# CANBUS.net
KiCad netlist of a schematic drawn in Altium Designer
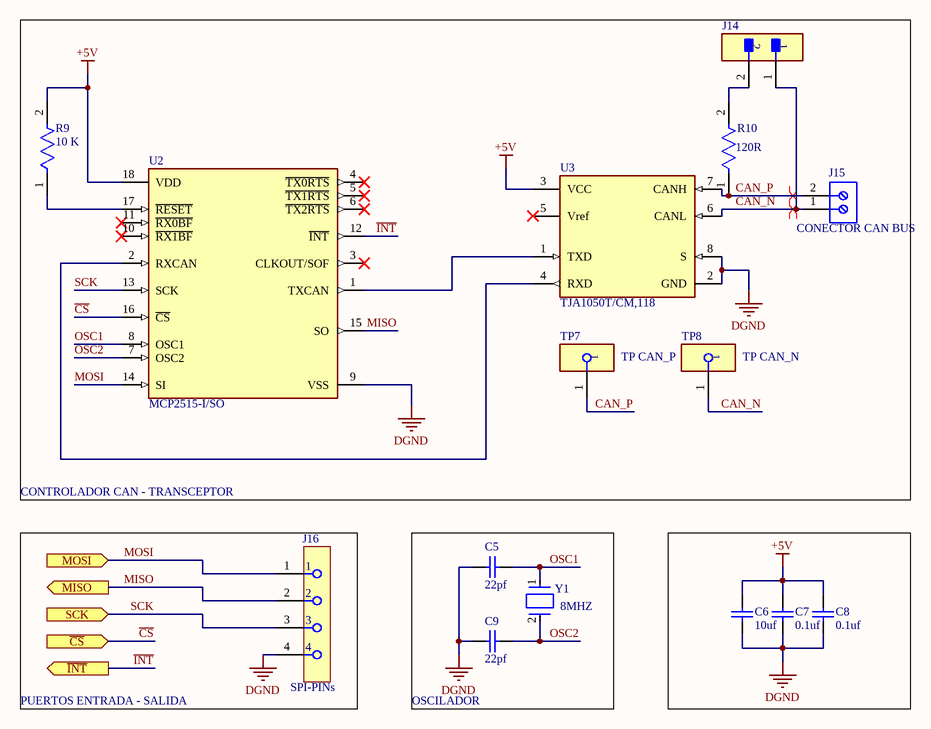
[diagram p0: CANBUS.SchDoc]

(export (version "E")
  (design (tool "Eeschema 10.0.6"))
  (components
    (comp (ref "C5")
      (value "22pf")
      (footprint "CAPC2013X145X50NL20T25")
      (description "CAP 22pf 20% 0805")
      (fields (field (name "MANUFACTURER") "Kemet") (field (name "PART NUMBER") "C0805S104K5RACTU"))
      (libsource (lib "Altium Content Vault") (part "CAP"))
    )
    (comp (ref "C6")
      (value "10uf")
      (footprint "CAPC2013X145X50NL20T25")
      (description "CAP 10uf 20% 0805")
      (fields (field (name "MANUFACTURER") "Kemet") (field (name "PART NUMBER") "C0805S104K5RACTU"))
      (libsource (lib "Altium Content Vault") (part "CAP"))
    )
    (comp (ref "C7")
      (value "0.1uf")
      (footprint "CAPC2013X145X50NL20T25")
      (description "CAP 100nf 20% 0805")
      (fields (field (name "MANUFACTURER") "Kemet") (field (name "PART NUMBER") "C0805S104K5RACTU"))
      (libsource (lib "Altium Content Vault") (part "CAP"))
    )
    (comp (ref "C8")
      (value "0.1uf")
      (footprint "CAPC2013X145X50NL20T25")
      (description "CAP 100nf 20% 0805")
      (fields (field (name "MANUFACTURER") "Kemet") (field (name "PART NUMBER") "C0805S104K5RACTU"))
      (libsource (lib "Altium Content Vault") (part "CAP"))
    )
    (comp (ref "C9")
      (value "22pf")
      (footprint "CAPC2013X145X50NL20T25")
      (description "CAP 22pf 20% 0805")
      (fields (field (name "MANUFACTURER") "Kemet") (field (name "PART NUMBER") "C0805S104K5RACTU"))
      (libsource (lib "Altium Content Vault") (part "CAP"))
    )
    (comp (ref "J14")
      (value "TSW-102-07-F-S")
      (footprint "FP-TSW-102-07-F-S-MFG")
      (description "HEADER PINS 2 POS / Jumper de Res. Terminacion")
      (libsource (lib "Altium Content Vault") (part "3bc925449376181038e59eaffc5286c"))
    )
    (comp (ref "J15")
      (value "CONECTOR CAN BUS")
      (footprint "691102710002")
      (description "TERMINAL BLOCK 2 POS / Salida BUS CAN")
      (fields (field (name "VOLTAGE") "300V"))
      (libsource (lib "Altium Content Vault") (part "TBL - 1R - 02P - Screw"))
    )
    (comp (ref "J16")
      (value "SPI-PINs")
      (footprint "FP-ESW-104-23-G-S-MFG")
      (description "HEADER PINS 4 POS / SPI Pins")
      (libsource (lib "Altium Content Vault") (part "ESW-104-23-G-S"))
    )
    (comp (ref "R9")
      (value "10 K")
      (footprint "FP-AC0805-MFG")
      (description "RES 10K 5% 0805")
      (fields
        (field (name "MANUFACTURER PART NUMBER") "AC0805FR-072K2L")
        (field (name "MANUFACTURER") "Yageo")
      )
      (libsource (lib "Altium Content Vault") (part "1029c3af85768c4190bb7ad29bc67b5"))
    )
    (comp (ref "R10")
      (value "120R")
      (footprint "FP-RN73R2A-IPC_A")
      (description "RES 120R 5% 0805 / Resistencia de terminacion")
      (libsource (lib "Altium Content Vault") (part "1029c3af85768c4190bb7ad29bc67b5"))
    )
    (comp (ref "TP7")
      (value "TP CAN_P")
      (footprint "FP-5004-MFG")
      (description "PC TEST POINT MINIATURE YELLOW")
      (fields (field (name "MANUFACTURER") "Keystone") (field (name "MANUFACTURER PART NUMBER") "5004"))
      (libsource (lib "Altium Content Vault") (part "98815daf2f2c152b0c43f5ab9800df6"))
    )
    (comp (ref "TP8")
      (value "TP CAN_N")
      (footprint "FP-5004-MFG")
      (description "PC TEST POINT MINIATURE YELLOW")
      (fields (field (name "MANUFACTURER") "Keystone") (field (name "MANUFACTURER PART NUMBER") "5004"))
      (libsource (lib "Altium Content Vault") (part "98815daf2f2c152b0c43f5ab9800df6"))
    )
    (comp (ref "U2")
      (value "MCP2515-I/SO")
      (footprint "FP-C04-051-MFG")
      (description "CI MCP2515 SOIC18")
      (fields
        (field (name "MANUFACTURER") "Microchip")
        (field (name "OCTOPART") "https://octopart.com/mcp2515-i%2Fso-microchip-430187")
      )
      (libsource (lib "Altium Content Vault") (part "1c78ea6ff576bac94664e2637e1b479"))
    )
    (comp (ref "U3")
      (value "TJA1050T/CM,118")
      (footprint "FP-SOT96-1-IPC_A")
      (description "CI TJA1050 TRANSCEIVER SOIC8")
      (libsource (lib "Altium Content Vault") (part "cfdefafd38a55dc0607790f57b8a78f"))
    )
    (comp (ref "Y1")
      (value "8MHZ")
      (footprint "FP-ECS-80-20-4X-MFG")
      (description "CRYSTAL 8 MHz / CAN BUS")
      (fields (field (name "TOLERANCE") "0.003%"))
      (libsource (lib "Altium Content Vault") (part "c23a69dc6c9e2f18f2079038eb95dd1"))
    )
  )
  (nets
    (net (code "1") (name "+5V") (class "Default")
      (node (ref "C6") (pin "2") (pinfunction "2_2") (pintype "passive"))
      (node (ref "C7") (pin "2") (pinfunction "2_2") (pintype "passive"))
      (node (ref "C8") (pin "2") (pinfunction "2_2") (pintype "passive"))
      (node (ref "R9") (pin "2") (pinfunction "2_2") (pintype "passive"))
      (node (ref "U2") (pin "18") (pinfunction "VDD_18") (pintype "power_in"))
      (node (ref "U3") (pin "3") (pinfunction "VCC_3") (pintype "power_in"))
    )
    (net (code "2") (name "/CAN_N") (class "Default")
      (node (ref "J14") (pin "1") (pinfunction "1_1") (pintype "passive"))
      (node (ref "J15") (pin "1") (pinfunction "1_1") (pintype "passive"))
      (node (ref "TP8") (pin "1") (pinfunction "1_1") (pintype "passive"))
      (node (ref "U3") (pin "6") (pinfunction "CANL_6") (pintype "input"))
    )
    (net (code "3") (name "/CAN_P") (class "Default")
      (node (ref "J15") (pin "2") (pinfunction "2_2") (pintype "passive"))
      (node (ref "R10") (pin "1") (pinfunction "1_1") (pintype "passive"))
      (node (ref "TP7") (pin "1") (pinfunction "1_1") (pintype "passive"))
      (node (ref "U3") (pin "7") (pinfunction "CANH_7") (pintype "input"))
    )
    (net (code "4") (name "/MISO") (class "Default")
      (node (ref "J16") (pin "2") (pinfunction "2_2") (pintype "passive"))
      (node (ref "U2") (pin "15") (pinfunction "SO_15") (pintype "output"))
    )
    (net (code "5") (name "/MOSI") (class "Default")
      (node (ref "J16") (pin "1") (pinfunction "1_1") (pintype "passive"))
      (node (ref "U2") (pin "14") (pinfunction "SI_14") (pintype "input"))
    )
    (net (code "6") (name "/OSC1") (class "Default")
      (node (ref "C5") (pin "2") (pinfunction "2_2") (pintype "passive"))
      (node (ref "U2") (pin "8") (pinfunction "OSC1_8") (pintype "input"))
      (node (ref "Y1") (pin "1") (pinfunction "1_1") (pintype "passive"))
    )
    (net (code "7") (name "/OSC2") (class "Default")
      (node (ref "C9") (pin "2") (pinfunction "2_2") (pintype "passive"))
      (node (ref "U2") (pin "7") (pinfunction "OSC2_7") (pintype "input"))
      (node (ref "Y1") (pin "2") (pinfunction "2_2") (pintype "passive"))
    )
    (net (code "8") (name "/SCK") (class "Default")
      (node (ref "J16") (pin "3") (pinfunction "3_3") (pintype "passive"))
      (node (ref "U2") (pin "13") (pinfunction "SCK_13") (pintype "input"))
    )
    (net (code "9") (name "/~{CS}") (class "Default")
      (node (ref "U2") (pin "16") (pinfunction "~{CS}_16") (pintype "input"))
    )
    (net (code "10") (name "/~{INT}") (class "Default")
      (node (ref "U2") (pin "12") (pinfunction "~{INT}_12") (pintype "output"))
    )
    (net (code "11") (name "DGND") (class "Default")
      (node (ref "C5") (pin "1") (pinfunction "1_1") (pintype "passive"))
      (node (ref "C6") (pin "1") (pinfunction "1_1") (pintype "passive"))
      (node (ref "C7") (pin "1") (pinfunction "1_1") (pintype "passive"))
      (node (ref "C8") (pin "1") (pinfunction "1_1") (pintype "passive"))
      (node (ref "C9") (pin "1") (pinfunction "1_1") (pintype "passive"))
      (node (ref "J16") (pin "4") (pinfunction "4_4") (pintype "passive"))
      (node (ref "U2") (pin "9") (pinfunction "VSS_9") (pintype "power_in"))
      (node (ref "U3") (pin "2") (pinfunction "GND_2") (pintype "power_in"))
      (node (ref "U3") (pin "8") (pinfunction "S_8") (pintype "input"))
    )
    (net (code "12") (name "Net-(J14-Pad2)") (class "Default")
      (node (ref "J14") (pin "2") (pinfunction "2_2") (pintype "passive"))
      (node (ref "R10") (pin "2") (pinfunction "2_2") (pintype "passive"))
    )
    (net (code "13") (name "Net-(U2-RXCAN)") (class "Default")
      (node (ref "U2") (pin "2") (pinfunction "RXCAN_2") (pintype "input"))
      (node (ref "U3") (pin "4") (pinfunction "RXD_4") (pintype "output"))
    )
    (net (code "14") (name "Net-(U2-TXCAN)") (class "Default")
      (node (ref "U2") (pin "1") (pinfunction "TXCAN_1") (pintype "output"))
      (node (ref "U3") (pin "1") (pinfunction "TXD_1") (pintype "input"))
    )
    (net (code "15") (name "Net-(U2-~{RESET})") (class "Default")
      (node (ref "R9") (pin "1") (pinfunction "1_1") (pintype "passive"))
      (node (ref "U2") (pin "17") (pinfunction "~{RESET}_17") (pintype "input"))
    )
    (net (code "16") (name "unconnected-(U2-CLKOUT{slash}SOF-Pad3)") (class "Default")
      (node (ref "U2") (pin "3") (pinfunction "CLKOUT/SOF_3") (pintype "output+no_connect"))
    )
    (net (code "17") (name "unconnected-(U2-~{RX0BF}-Pad11)") (class "Default")
      (node (ref "U2") (pin "11") (pinfunction "~{RX0BF}_11") (pintype "input+no_connect"))
    )
    (net (code "18") (name "unconnected-(U2-~{RX1BF}-Pad10)") (class "Default")
      (node (ref "U2") (pin "10") (pinfunction "~{RX1BF}_10") (pintype "input+no_connect"))
    )
    (net (code "19") (name "unconnected-(U2-~{TX0RTS}-Pad4)") (class "Default")
      (node (ref "U2") (pin "4") (pinfunction "~{TX0RTS}_4") (pintype "output+no_connect"))
    )
    (net (code "20") (name "unconnected-(U2-~{TX1RTS}-Pad5)") (class "Default")
      (node (ref "U2") (pin "5") (pinfunction "~{TX1RTS}_5") (pintype "output+no_connect"))
    )
    (net (code "21") (name "unconnected-(U2-~{TX2RTS}-Pad6)") (class "Default")
      (node (ref "U2") (pin "6") (pinfunction "~{TX2RTS}_6") (pintype "output+no_connect"))
    )
    (net (code "22") (name "unconnected-(U3-Vref-Pad5)") (class "Default")
      (node (ref "U3") (pin "5") (pinfunction "Vref_5") (pintype "power_in+no_connect"))
    )
  )
)
